# MainBoardR1.net
KiCad netlist of a schematic drawn in EAGLE
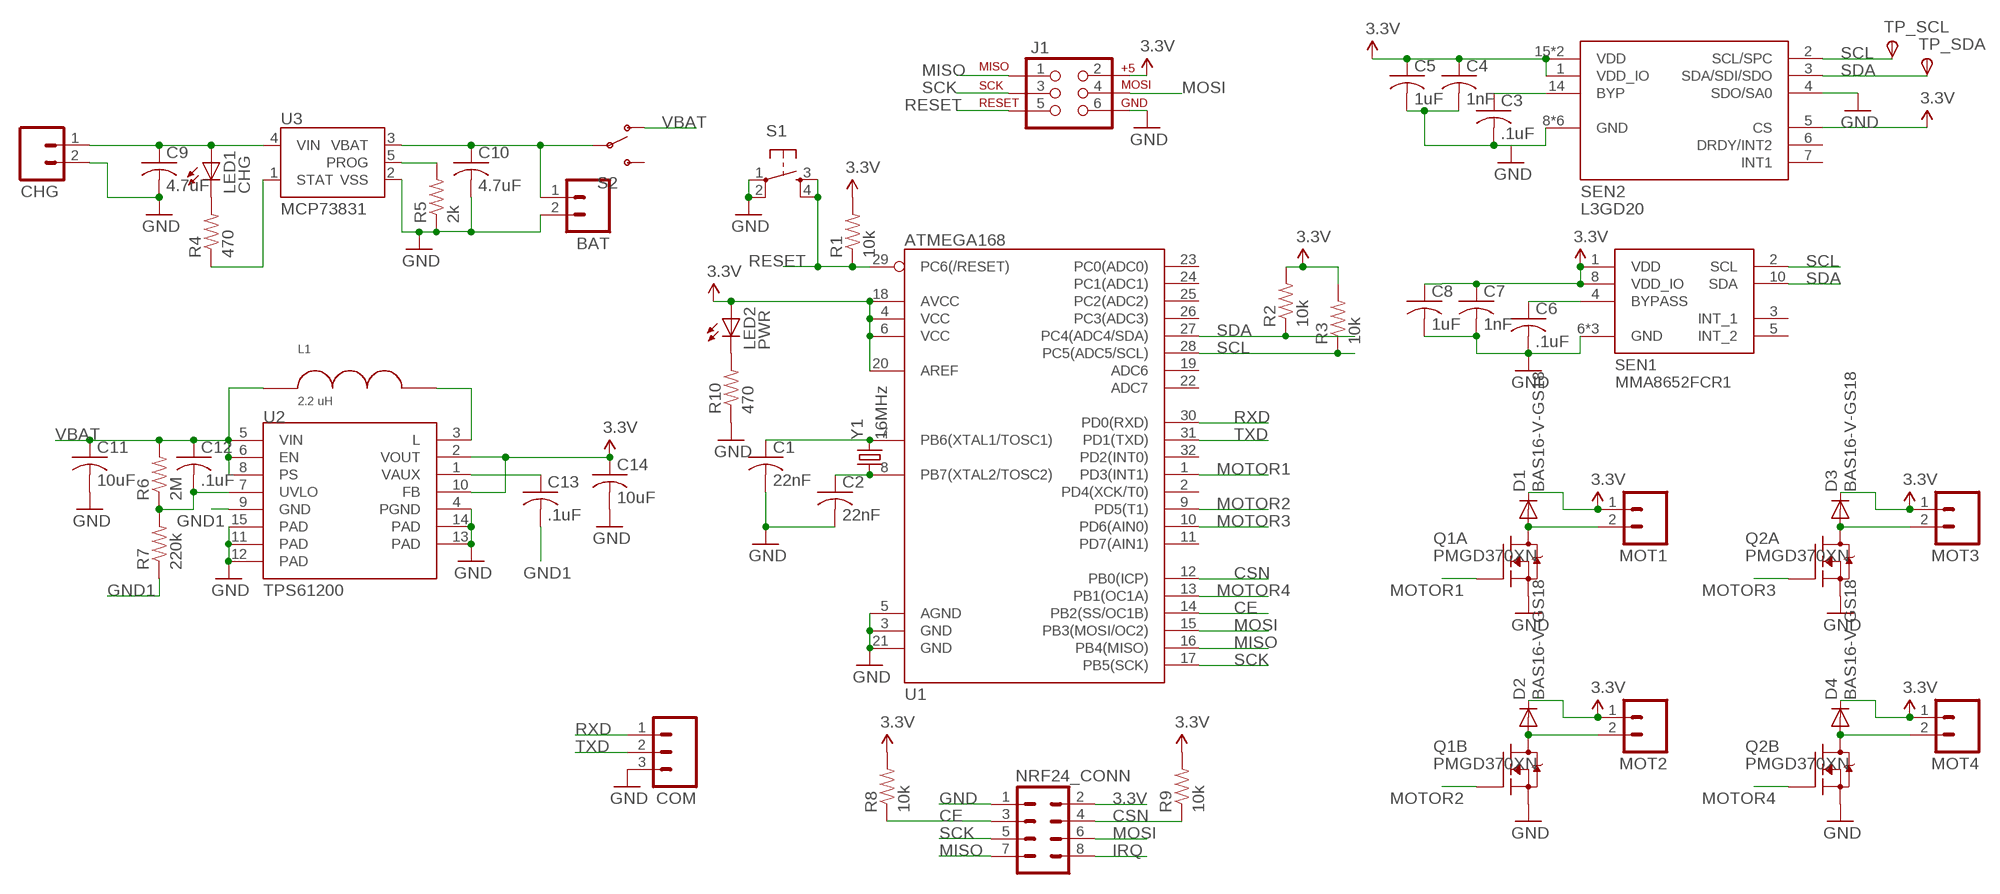
[diagram p0: schematic, sheet 1]

(export (version "E")
  (design (tool "Eeschema 10.0.6"))
  (components
    (comp (ref "BAT")
      (value "M02LOCK_LONGPADS")
      (footprint "eagle-import:1X02_LOCK_LONGPADS")
      (libsource (lib "eagle-import") (part "M02LOCK_LONGPADS"))
    )
    (comp (ref "C1")
      (value "22nF")
      (footprint "eagle-import:C0805")
      (libsource (lib "eagle-import") (part "C-USC0805"))
    )
    (comp (ref "C2")
      (value "22nF")
      (footprint "eagle-import:C0805")
      (libsource (lib "eagle-import") (part "C-USC0805"))
    )
    (comp (ref "C3")
      (value ".1uF")
      (footprint "eagle-import:C0805")
      (libsource (lib "eagle-import") (part "C-USC0805"))
    )
    (comp (ref "C4")
      (value "1nF")
      (footprint "eagle-import:C0805")
      (libsource (lib "eagle-import") (part "C-USC0805"))
    )
    (comp (ref "C5")
      (value "1uF")
      (footprint "eagle-import:C0805")
      (libsource (lib "eagle-import") (part "C-USC0805"))
    )
    (comp (ref "C6")
      (value ".1uF")
      (footprint "eagle-import:C0805")
      (libsource (lib "eagle-import") (part "C-USC0805"))
    )
    (comp (ref "C7")
      (value "1nF")
      (footprint "eagle-import:C0805")
      (libsource (lib "eagle-import") (part "C-USC0805"))
    )
    (comp (ref "C8")
      (value "1uF")
      (footprint "eagle-import:C0805")
      (libsource (lib "eagle-import") (part "C-USC0805"))
    )
    (comp (ref "C9")
      (value "4.7uF")
      (footprint "eagle-import:C0805")
      (libsource (lib "eagle-import") (part "C-USC0805"))
    )
    (comp (ref "C10")
      (value "4.7uF")
      (footprint "eagle-import:C0805")
      (libsource (lib "eagle-import") (part "C-USC0805"))
    )
    (comp (ref "C11")
      (value "10uF")
      (footprint "eagle-import:C0805")
      (libsource (lib "eagle-import") (part "C-USC0805"))
    )
    (comp (ref "C12")
      (value ".1uF")
      (footprint "eagle-import:C0805")
      (libsource (lib "eagle-import") (part "C-USC0805"))
    )
    (comp (ref "C13")
      (value ".1uF")
      (footprint "eagle-import:C0805")
      (libsource (lib "eagle-import") (part "C-USC0805"))
    )
    (comp (ref "C14")
      (value "10uF")
      (footprint "eagle-import:C0805")
      (libsource (lib "eagle-import") (part "C-USC0805"))
    )
    (comp (ref "CHG")
      (value "M02LOCK_LONGPADS")
      (footprint "eagle-import:1X02_LOCK_LONGPADS")
      (libsource (lib "eagle-import") (part "M02LOCK_LONGPADS"))
    )
    (comp (ref "COM")
      (value "M03LONGPADS")
      (footprint "eagle-import:1X03_LONGPADS")
      (libsource (lib "eagle-import") (part "M03LONGPADS"))
    )
    (comp (ref "D1")
      (value "BAS16-V-GS18")
      (footprint "eagle-import:SOT23")
      (libsource (lib "eagle-import") (part "BAS16-V-GS18"))
    )
    (comp (ref "D2")
      (value "BAS16-V-GS18")
      (footprint "eagle-import:SOT23")
      (libsource (lib "eagle-import") (part "BAS16-V-GS18"))
    )
    (comp (ref "D3")
      (value "BAS16-V-GS18")
      (footprint "eagle-import:SOT23")
      (libsource (lib "eagle-import") (part "BAS16-V-GS18"))
    )
    (comp (ref "D4")
      (value "BAS16-V-GS18")
      (footprint "eagle-import:SOT23")
      (libsource (lib "eagle-import") (part "BAS16-V-GS18"))
    )
    (comp (ref "J1")
      (value "AVR_SPI_PRG_62X3_LOCK")
      (footprint "eagle-import:2X3_LOCK")
      (libsource (lib "eagle-import") (part "AVR_SPI_PRG_62X3_LOCK"))
    )
    (comp (ref "L1")
      (value "2.2 uH")
      (footprint "eagle-import:2518")
      (libsource (lib "eagle-import") (part "BRHL2518T2R2M"))
    )
    (comp (ref "LED1")
      (value "CHG")
      (footprint "eagle-import:LED-1206")
      (libsource (lib "eagle-import") (part "LED1206"))
    )
    (comp (ref "LED2")
      (value "PWR")
      (footprint "eagle-import:LED-1206")
      (libsource (lib "eagle-import") (part "LED1206"))
    )
    (comp (ref "MOT1")
      (value "M02LOCK_LONGPADS")
      (footprint "eagle-import:1X02_LOCK_LONGPADS")
      (libsource (lib "eagle-import") (part "M02LOCK_LONGPADS"))
    )
    (comp (ref "MOT2")
      (value "M02LOCK_LONGPADS")
      (footprint "eagle-import:1X02_LOCK_LONGPADS")
      (libsource (lib "eagle-import") (part "M02LOCK_LONGPADS"))
    )
    (comp (ref "MOT3")
      (value "M02LOCK_LONGPADS")
      (footprint "eagle-import:1X02_LOCK_LONGPADS")
      (libsource (lib "eagle-import") (part "M02LOCK_LONGPADS"))
    )
    (comp (ref "MOT4")
      (value "M02LOCK_LONGPADS")
      (footprint "eagle-import:1X02_LOCK_LONGPADS")
      (libsource (lib "eagle-import") (part "M02LOCK_LONGPADS"))
    )
    (comp (ref "NRF24_CONN")
      (value "M04X2")
      (footprint "eagle-import:2X4")
      (libsource (lib "eagle-import") (part "M04X2"))
    )
    (comp (ref "Q1")
      (value "PMGD370XN")
      (footprint "eagle-import:SOT363_INFINEON")
      (libsource (lib "eagle-import") (part "PMGD370XN"))
    )
    (comp (ref "Q2")
      (value "PMGD370XN")
      (footprint "eagle-import:SOT363_INFINEON")
      (libsource (lib "eagle-import") (part "PMGD370XN"))
    )
    (comp (ref "R1")
      (value "10k")
      (footprint "eagle-import:0805")
      (libsource (lib "eagle-import") (part "RESISTOR0805-RES"))
    )
    (comp (ref "R2")
      (value "10k")
      (footprint "eagle-import:0805")
      (libsource (lib "eagle-import") (part "RESISTOR0805-RES"))
    )
    (comp (ref "R3")
      (value "10k")
      (footprint "eagle-import:0805")
      (libsource (lib "eagle-import") (part "RESISTOR0805-RES"))
    )
    (comp (ref "R4")
      (value "470")
      (footprint "eagle-import:0805")
      (libsource (lib "eagle-import") (part "RESISTOR0805-RES"))
    )
    (comp (ref "R5")
      (value "2k")
      (footprint "eagle-import:0805")
      (libsource (lib "eagle-import") (part "RESISTOR0805-RES"))
    )
    (comp (ref "R6")
      (value "2M")
      (footprint "eagle-import:0805")
      (libsource (lib "eagle-import") (part "RESISTOR0805-RES"))
    )
    (comp (ref "R7")
      (value "220k")
      (footprint "eagle-import:0805")
      (libsource (lib "eagle-import") (part "RESISTOR0805-RES"))
    )
    (comp (ref "R8")
      (value "10k")
      (footprint "eagle-import:0805")
      (libsource (lib "eagle-import") (part "RESISTOR0805-RES"))
    )
    (comp (ref "R9")
      (value "10k")
      (footprint "eagle-import:0805")
      (libsource (lib "eagle-import") (part "RESISTOR0805-RES"))
    )
    (comp (ref "R10")
      (value "470")
      (footprint "eagle-import:0805")
      (libsource (lib "eagle-import") (part "RESISTOR0805-RES"))
    )
    (comp (ref "S1")
      (value "TAC_SWITCHSMD")
      (footprint "eagle-import:TACTILE_SWITCH_SMD")
      (libsource (lib "eagle-import") (part "TAC_SWITCHSMD"))
    )
    (comp (ref "S2")
      (value "SWITCH-SPST-SMD-A")
      (footprint "eagle-import:SWITCH-SPST-SMD-A")
      (libsource (lib "eagle-import") (part "SWITCH-SPST-SMD-A"))
    )
    (comp (ref "SEN1")
      (value "MMA8652FCR1")
      (footprint "eagle-import:10_PIN_DFN")
      (libsource (lib "eagle-import") (part "MMA8652FCR1"))
    )
    (comp (ref "SEN2")
      (value "L3GD20")
      (footprint "eagle-import:LGA-16")
      (libsource (lib "eagle-import") (part "L3GD20"))
    )
    (comp (ref "TP_SCL")
      (value "TPSTP14SQ")
      (footprint "eagle-import:TP14SQ")
      (libsource (lib "eagle-import") (part "TPSTP14SQ"))
    )
    (comp (ref "TP_SDA")
      (value "TPSTP14SQ")
      (footprint "eagle-import:TP14SQ")
      (libsource (lib "eagle-import") (part "TPSTP14SQ"))
    )
    (comp (ref "U1")
      (value "ATMEGA168")
      (footprint "eagle-import:TQFP32-08")
      (libsource (lib "eagle-import") (part "ATMEGA168"))
    )
    (comp (ref "U2")
      (value "TPS61200")
      (footprint "eagle-import:QFN-10_PAD")
      (libsource (lib "eagle-import") (part "TPS61200"))
    )
    (comp (ref "U3")
      (value "MCP73831")
      (footprint "eagle-import:SOT23-5")
      (libsource (lib "eagle-import") (part "MCP73831"))
    )
    (comp (ref "Y1")
      (value "16MHz")
      (footprint "eagle-import:CRYSTAL-SMD-5X3")
      (libsource (lib "eagle-import") (part "CRYSTAL5X3"))
    )
  )
  (nets
    (net (code "1") (name "/CE") (class "Default")
      (node (ref "NRF24_CONN") (pin "3") (pinfunction "3_3") (pintype "passive"))
      (node (ref "R8") (pin "1") (pinfunction "1_1") (pintype "passive"))
      (node (ref "U1") (pin "14") (pinfunction "PB2(SS/OC1B)_14") (pintype "bidirectional"))
    )
    (net (code "2") (name "/CSN") (class "Default")
      (node (ref "NRF24_CONN") (pin "4") (pinfunction "4_4") (pintype "passive"))
      (node (ref "R9") (pin "1") (pinfunction "1_1") (pintype "passive"))
      (node (ref "U1") (pin "12") (pinfunction "PB0(ICP)_12") (pintype "bidirectional"))
    )
    (net (code "3") (name "/GND1") (class "Default")
      (node (ref "C13") (pin "2") (pinfunction "2_2") (pintype "passive"))
      (node (ref "R7") (pin "1") (pinfunction "1_1") (pintype "passive"))
      (node (ref "U2") (pin "9") (pinfunction "GND_9") (pintype "power_in"))
    )
    (net (code "4") (name "/IRQ") (class "Default")
      (node (ref "NRF24_CONN") (pin "8") (pinfunction "8_8") (pintype "passive"))
    )
    (net (code "5") (name "/MISO") (class "Default")
      (node (ref "J1") (pin "1") (pinfunction "1_1") (pintype "passive"))
      (node (ref "NRF24_CONN") (pin "7") (pinfunction "7_7") (pintype "passive"))
      (node (ref "U1") (pin "16") (pinfunction "PB4(MISO)_16") (pintype "bidirectional"))
    )
    (net (code "6") (name "/MOSI") (class "Default")
      (node (ref "J1") (pin "4") (pinfunction "4_4") (pintype "passive"))
      (node (ref "NRF24_CONN") (pin "6") (pinfunction "6_6") (pintype "passive"))
      (node (ref "U1") (pin "15") (pinfunction "PB3(MOSI/OC2)_15") (pintype "bidirectional"))
    )
    (net (code "7") (name "/MOTOR1") (class "Default")
      (node (ref "Q1") (pin "2") (pinfunction "G_2") (pintype "passive"))
      (node (ref "U1") (pin "1") (pinfunction "PD3(INT1)_1") (pintype "bidirectional"))
    )
    (net (code "8") (name "/MOTOR2") (class "Default")
      (node (ref "Q1") (pin "5") (pinfunction "G_5") (pintype "passive"))
      (node (ref "U1") (pin "9") (pinfunction "PD5(T1)_9") (pintype "bidirectional"))
    )
    (net (code "9") (name "/MOTOR3") (class "Default")
      (node (ref "Q2") (pin "2") (pinfunction "G_2") (pintype "passive"))
      (node (ref "U1") (pin "10") (pinfunction "PD6(AIN0)_10") (pintype "bidirectional"))
    )
    (net (code "10") (name "/MOTOR4") (class "Default")
      (node (ref "Q2") (pin "5") (pinfunction "G_5") (pintype "passive"))
      (node (ref "U1") (pin "13") (pinfunction "PB1(OC1A)_13") (pintype "bidirectional"))
    )
    (net (code "11") (name "/RESET") (class "Default")
      (node (ref "J1") (pin "5") (pinfunction "5_5") (pintype "passive"))
      (node (ref "R1") (pin "1") (pinfunction "1_1") (pintype "passive"))
      (node (ref "S1") (pin "3") (pinfunction "3_3") (pintype "passive"))
      (node (ref "S1") (pin "4") (pinfunction "4_4") (pintype "passive"))
      (node (ref "U1") (pin "29") (pinfunction "PC6(/RESET)_29") (pintype "bidirectional"))
    )
    (net (code "12") (name "/RXD") (class "Default")
      (node (ref "COM") (pin "1") (pinfunction "1_1") (pintype "passive"))
      (node (ref "U1") (pin "30") (pinfunction "PD0(RXD)_30") (pintype "bidirectional"))
    )
    (net (code "13") (name "/SCK") (class "Default")
      (node (ref "J1") (pin "3") (pinfunction "3_3") (pintype "passive"))
      (node (ref "NRF24_CONN") (pin "5") (pinfunction "5_5") (pintype "passive"))
      (node (ref "U1") (pin "17") (pinfunction "PB5(SCK)_17") (pintype "bidirectional"))
    )
    (net (code "14") (name "/SCL") (class "Default")
      (node (ref "R3") (pin "1") (pinfunction "1_1") (pintype "passive"))
      (node (ref "SEN1") (pin "2") (pinfunction "SCL_2") (pintype "bidirectional"))
      (node (ref "SEN2") (pin "2") (pinfunction "SCL/SPC_2") (pintype "bidirectional"))
      (node (ref "TP_SCL") (pin "TP") (pinfunction "PP_TP") (pintype "input"))
      (node (ref "U1") (pin "28") (pinfunction "PC5(ADC5/SCL)_28") (pintype "bidirectional"))
    )
    (net (code "15") (name "/SDA") (class "Default")
      (node (ref "R2") (pin "1") (pinfunction "1_1") (pintype "passive"))
      (node (ref "SEN1") (pin "10") (pinfunction "SDA_10") (pintype "bidirectional"))
      (node (ref "SEN2") (pin "3") (pinfunction "SDA/SDI/SDO_3") (pintype "bidirectional"))
      (node (ref "TP_SDA") (pin "TP") (pinfunction "PP_TP") (pintype "input"))
      (node (ref "U1") (pin "27") (pinfunction "PC4(ADC4/SDA)_27") (pintype "bidirectional"))
    )
    (net (code "16") (name "/TXD") (class "Default")
      (node (ref "COM") (pin "2") (pinfunction "2_2") (pintype "passive"))
      (node (ref "U1") (pin "31") (pinfunction "PD1(TXD)_31") (pintype "bidirectional"))
    )
    (net (code "17") (name "/VBAT") (class "Default")
      (node (ref "C11") (pin "1") (pinfunction "1_1") (pintype "passive"))
      (node (ref "C12") (pin "1") (pinfunction "1_1") (pintype "passive"))
      (node (ref "L1") (pin "P$1") (pinfunction "1_P$1") (pintype "bidirectional"))
      (node (ref "R6") (pin "2") (pinfunction "2_2") (pintype "passive"))
      (node (ref "S2") (pin "1") (pinfunction "O_1") (pintype "passive"))
      (node (ref "U2") (pin "5") (pinfunction "VIN_5") (pintype "power_in"))
      (node (ref "U2") (pin "6") (pinfunction "EN_6") (pintype "input"))
      (node (ref "U2") (pin "8") (pinfunction "PS_8") (pintype "input"))
    )
    (net (code "18") (name "3.3V") (class "Default")
      (node (ref "C14") (pin "1") (pinfunction "1_1") (pintype "passive"))
      (node (ref "C4") (pin "1") (pinfunction "1_1") (pintype "passive"))
      (node (ref "C5") (pin "1") (pinfunction "1_1") (pintype "passive"))
      (node (ref "C7") (pin "1") (pinfunction "1_1") (pintype "passive"))
      (node (ref "C8") (pin "1") (pinfunction "1_1") (pintype "passive"))
      (node (ref "D1") (pin "3") (pinfunction "C_3") (pintype "passive"))
      (node (ref "D2") (pin "3") (pinfunction "C_3") (pintype "passive"))
      (node (ref "D3") (pin "3") (pinfunction "C_3") (pintype "passive"))
      (node (ref "D4") (pin "3") (pinfunction "C_3") (pintype "passive"))
      (node (ref "J1") (pin "2") (pinfunction "2_2") (pintype "passive"))
      (node (ref "LED2") (pin "A") (pinfunction "A_A") (pintype "passive"))
      (node (ref "MOT1") (pin "1") (pinfunction "1_1") (pintype "passive"))
      (node (ref "MOT2") (pin "1") (pinfunction "1_1") (pintype "passive"))
      (node (ref "MOT3") (pin "1") (pinfunction "1_1") (pintype "passive"))
      (node (ref "MOT4") (pin "1") (pinfunction "1_1") (pintype "passive"))
      (node (ref "NRF24_CONN") (pin "2") (pinfunction "2_2") (pintype "passive"))
      (node (ref "R1") (pin "2") (pinfunction "2_2") (pintype "passive"))
      (node (ref "R2") (pin "2") (pinfunction "2_2") (pintype "passive"))
      (node (ref "R3") (pin "2") (pinfunction "2_2") (pintype "passive"))
      (node (ref "R8") (pin "2") (pinfunction "2_2") (pintype "passive"))
      (node (ref "R9") (pin "2") (pinfunction "2_2") (pintype "passive"))
      (node (ref "SEN1") (pin "1") (pinfunction "VDD_1") (pintype "bidirectional"))
      (node (ref "SEN1") (pin "8") (pinfunction "VDD_IO_8") (pintype "bidirectional"))
      (node (ref "SEN2") (pin "1") (pinfunction "VDD_IO_1") (pintype "bidirectional"))
      (node (ref "SEN2") (pin "15") (pinfunction "VDD_15") (pintype "bidirectional"))
      (node (ref "SEN2") (pin "16") (pinfunction "VDD_16") (pintype "bidirectional"))
      (node (ref "SEN2") (pin "5") (pinfunction "CS_5") (pintype "bidirectional"))
      (node (ref "U1") (pin "18") (pinfunction "AVCC_18") (pintype "bidirectional"))
      (node (ref "U1") (pin "20") (pinfunction "AREF_20") (pintype "bidirectional"))
      (node (ref "U1") (pin "4") (pinfunction "VCC_4") (pintype "bidirectional"))
      (node (ref "U1") (pin "6") (pinfunction "VCC_6") (pintype "bidirectional"))
      (node (ref "U2") (pin "10") (pinfunction "FB_10") (pintype "passive"))
      (node (ref "U2") (pin "2") (pinfunction "VOUT_2") (pintype "passive"))
    )
    (net (code "19") (name "GND") (class "Default")
      (node (ref "BAT") (pin "2") (pinfunction "2_2") (pintype "passive"))
      (node (ref "C1") (pin "2") (pinfunction "2_2") (pintype "passive"))
      (node (ref "C10") (pin "2") (pinfunction "2_2") (pintype "passive"))
      (node (ref "C11") (pin "2") (pinfunction "2_2") (pintype "passive"))
      (node (ref "C14") (pin "2") (pinfunction "2_2") (pintype "passive"))
      (node (ref "C2") (pin "2") (pinfunction "2_2") (pintype "passive"))
      (node (ref "C3") (pin "2") (pinfunction "2_2") (pintype "passive"))
      (node (ref "C4") (pin "2") (pinfunction "2_2") (pintype "passive"))
      (node (ref "C5") (pin "2") (pinfunction "2_2") (pintype "passive"))
      (node (ref "C6") (pin "2") (pinfunction "2_2") (pintype "passive"))
      (node (ref "C7") (pin "2") (pinfunction "2_2") (pintype "passive"))
      (node (ref "C8") (pin "2") (pinfunction "2_2") (pintype "passive"))
      (node (ref "C9") (pin "2") (pinfunction "2_2") (pintype "passive"))
      (node (ref "CHG") (pin "2") (pinfunction "2_2") (pintype "passive"))
      (node (ref "COM") (pin "3") (pinfunction "3_3") (pintype "passive"))
      (node (ref "J1") (pin "6") (pinfunction "6_6") (pintype "passive"))
      (node (ref "NRF24_CONN") (pin "1") (pinfunction "1_1") (pintype "passive"))
      (node (ref "Q1") (pin "1") (pinfunction "S_1") (pintype "passive"))
      (node (ref "Q1") (pin "4") (pinfunction "S_4") (pintype "passive"))
      (node (ref "Q2") (pin "1") (pinfunction "S_1") (pintype "passive"))
      (node (ref "Q2") (pin "4") (pinfunction "S_4") (pintype "passive"))
      (node (ref "R10") (pin "1") (pinfunction "1_1") (pintype "passive"))
      (node (ref "R5") (pin "1") (pinfunction "1_1") (pintype "passive"))
      (node (ref "S1") (pin "1") (pinfunction "1_1") (pintype "passive"))
      (node (ref "S1") (pin "2") (pinfunction "2_2") (pintype "passive"))
      (node (ref "SEN1") (pin "6") (pinfunction "GND_6") (pintype "bidirectional"))
      (node (ref "SEN1") (pin "7") (pinfunction "GND_7") (pintype "bidirectional"))
      (node (ref "SEN1") (pin "9") (pinfunction "GND_9") (pintype "bidirectional"))
      (node (ref "SEN2") (pin "10") (pinfunction "GND_10") (pintype "bidirectional"))
      (node (ref "SEN2") (pin "11") (pinfunction "GND_11") (pintype "bidirectional"))
      (node (ref "SEN2") (pin "12") (pinfunction "GND_12") (pintype "bidirectional"))
      (node (ref "SEN2") (pin "13") (pinfunction "GND_13") (pintype "bidirectional"))
      (node (ref "SEN2") (pin "4") (pinfunction "SDO/SA0_4") (pintype "bidirectional"))
      (node (ref "SEN2") (pin "8") (pinfunction "GND_8") (pintype "bidirectional"))
      (node (ref "SEN2") (pin "9") (pinfunction "GND_9") (pintype "bidirectional"))
      (node (ref "U1") (pin "21") (pinfunction "GND_21") (pintype "bidirectional"))
      (node (ref "U1") (pin "3") (pinfunction "GND_3") (pintype "bidirectional"))
      (node (ref "U1") (pin "5") (pinfunction "AGND_5") (pintype "bidirectional"))
      (node (ref "U2") (pin "11") (pinfunction "PAD_11") (pintype "power_in"))
      (node (ref "U2") (pin "12") (pinfunction "PAD_12") (pintype "power_in"))
      (node (ref "U2") (pin "13") (pinfunction "PAD_13") (pintype "power_in"))
      (node (ref "U2") (pin "14") (pinfunction "PAD_14") (pintype "power_in"))
      (node (ref "U2") (pin "15") (pinfunction "PAD_15") (pintype "power_in"))
      (node (ref "U2") (pin "4") (pinfunction "PGND_4") (pintype "power_in"))
      (node (ref "U3") (pin "2") (pinfunction "VSS_2") (pintype "power_in"))
    )
    (net (code "20") (name "Net-(D1-A)") (class "Default")
      (node (ref "D1") (pin "1") (pinfunction "A_1") (pintype "passive"))
      (node (ref "MOT1") (pin "2") (pinfunction "2_2") (pintype "passive"))
      (node (ref "Q1") (pin "6") (pinfunction "D_6") (pintype "passive"))
    )
    (net (code "21") (name "Net-(D2-A)") (class "Default")
      (node (ref "D2") (pin "1") (pinfunction "A_1") (pintype "passive"))
      (node (ref "MOT2") (pin "2") (pinfunction "2_2") (pintype "passive"))
      (node (ref "Q1") (pin "3") (pinfunction "D_3") (pintype "passive"))
    )
    (net (code "22") (name "Net-(D3-A)") (class "Default")
      (node (ref "D3") (pin "1") (pinfunction "A_1") (pintype "passive"))
      (node (ref "MOT3") (pin "2") (pinfunction "2_2") (pintype "passive"))
      (node (ref "Q2") (pin "6") (pinfunction "D_6") (pintype "passive"))
    )
    (net (code "23") (name "Net-(D4-A)") (class "Default")
      (node (ref "D4") (pin "1") (pinfunction "A_1") (pintype "passive"))
      (node (ref "MOT4") (pin "2") (pinfunction "2_2") (pintype "passive"))
      (node (ref "Q2") (pin "3") (pinfunction "D_3") (pintype "passive"))
    )
    (net (code "24") (name "Net-(L1-2)") (class "Default")
      (node (ref "L1") (pin "P$2") (pinfunction "2_P$2") (pintype "bidirectional"))
      (node (ref "U2") (pin "3") (pinfunction "L_3") (pintype "passive"))
    )
    (net (code "25") (name "Net-(LED1-PadC)") (class "Default")
      (node (ref "LED1") (pin "C") (pinfunction "C_C") (pintype "passive"))
      (node (ref "R4") (pin "2") (pinfunction "2_2") (pintype "passive"))
    )
    (net (code "26") (name "Net-(LED2-PadC)") (class "Default")
      (node (ref "LED2") (pin "C") (pinfunction "C_C") (pintype "passive"))
      (node (ref "R10") (pin "2") (pinfunction "2_2") (pintype "passive"))
    )
    (net (code "27") (name "Net-(S2-P)") (class "Default")
      (node (ref "BAT") (pin "1") (pinfunction "1_1") (pintype "passive"))
      (node (ref "C10") (pin "1") (pinfunction "1_1") (pintype "passive"))
      (node (ref "S2") (pin "2") (pinfunction "P_2") (pintype "passive"))
      (node (ref "U3") (pin "3") (pinfunction "VBAT_3") (pintype "power_in"))
    )
    (net (code "28") (name "Net-(SEN1-BYPASS)") (class "Default")
      (node (ref "C6") (pin "1") (pinfunction "1_1") (pintype "passive"))
      (node (ref "SEN1") (pin "4") (pinfunction "BYPASS_4") (pintype "bidirectional"))
    )
    (net (code "29") (name "Net-(SEN2-BYP)") (class "Default")
      (node (ref "C3") (pin "1") (pinfunction "1_1") (pintype "passive"))
      (node (ref "SEN2") (pin "14") (pinfunction "BYP_14") (pintype "bidirectional"))
    )
    (net (code "30") (name "Net-(U1-PB6(XTAL1{slash}TOSC1))") (class "Default")
      (node (ref "C1") (pin "1") (pinfunction "1_1") (pintype "passive"))
      (node (ref "U1") (pin "7") (pinfunction "PB6(XTAL1/TOSC1)_7") (pintype "bidirectional"))
      (node (ref "Y1") (pin "3") (pinfunction "2_3") (pintype "passive"))
    )
    (net (code "31") (name "Net-(U1-PB7(XTAL2{slash}TOSC2))") (class "Default")
      (node (ref "C2") (pin "1") (pinfunction "1_1") (pintype "passive"))
      (node (ref "U1") (pin "8") (pinfunction "PB7(XTAL2/TOSC2)_8") (pintype "bidirectional"))
      (node (ref "Y1") (pin "1") (pinfunction "1_1") (pintype "passive"))
    )
    (net (code "32") (name "Net-(U2-UVLO)") (class "Default")
      (node (ref "C12") (pin "2") (pinfunction "2_2") (pintype "passive"))
      (node (ref "R6") (pin "1") (pinfunction "1_1") (pintype "passive"))
      (node (ref "R7") (pin "2") (pinfunction "2_2") (pintype "passive"))
      (node (ref "U2") (pin "7") (pinfunction "UVLO_7") (pintype "passive"))
    )
    (net (code "33") (name "Net-(U2-VAUX)") (class "Default")
      (node (ref "C13") (pin "1") (pinfunction "1_1") (pintype "passive"))
      (node (ref "U2") (pin "1") (pinfunction "VAUX_1") (pintype "passive"))
    )
    (net (code "34") (name "Net-(U3-PROG)") (class "Default")
      (node (ref "R5") (pin "2") (pinfunction "2_2") (pintype "passive"))
      (node (ref "U3") (pin "5") (pinfunction "PROG_5") (pintype "input"))
    )
    (net (code "35") (name "Net-(U3-STAT)") (class "Default")
      (node (ref "R4") (pin "1") (pinfunction "1_1") (pintype "passive"))
      (node (ref "U3") (pin "1") (pinfunction "STAT_1") (pintype "output"))
    )
    (net (code "36") (name "Net-(U3-VIN)") (class "Default")
      (node (ref "C9") (pin "1") (pinfunction "1_1") (pintype "passive"))
      (node (ref "CHG") (pin "1") (pinfunction "1_1") (pintype "passive"))
      (node (ref "LED1") (pin "A") (pinfunction "A_A") (pintype "passive"))
      (node (ref "U3") (pin "4") (pinfunction "VIN_4") (pintype "power_in"))
    )
    (net (code "37") (name "unconnected-(S2-S-Pad3)") (class "Default")
      (node (ref "S2") (pin "3") (pinfunction "S_3") (pintype "passive"))
    )
    (net (code "38") (name "unconnected-(SEN1-INT_1-Pad3)") (class "Default")
      (node (ref "SEN1") (pin "3") (pinfunction "INT_1_3") (pintype "bidirectional"))
    )
    (net (code "39") (name "unconnected-(SEN1-INT_2-Pad5)") (class "Default")
      (node (ref "SEN1") (pin "5") (pinfunction "INT_2_5") (pintype "bidirectional"))
    )
    (net (code "40") (name "unconnected-(SEN2-DRDY{slash}INT2-Pad6)") (class "Default")
      (node (ref "SEN2") (pin "6") (pinfunction "DRDY/INT2_6") (pintype "bidirectional"))
    )
    (net (code "41") (name "unconnected-(SEN2-INT1-Pad7)") (class "Default")
      (node (ref "SEN2") (pin "7") (pinfunction "INT1_7") (pintype "bidirectional"))
    )
    (net (code "42") (name "unconnected-(U1-ADC6-Pad19)") (class "Default")
      (node (ref "U1") (pin "19") (pinfunction "ADC6_19") (pintype "bidirectional"))
    )
    (net (code "43") (name "unconnected-(U1-ADC7-Pad22)") (class "Default")
      (node (ref "U1") (pin "22") (pinfunction "ADC7_22") (pintype "bidirectional"))
    )
    (net (code "44") (name "unconnected-(U1-PC0(ADC0)-Pad23)") (class "Default")
      (node (ref "U1") (pin "23") (pinfunction "PC0(ADC0)_23") (pintype "bidirectional"))
    )
    (net (code "45") (name "unconnected-(U1-PC1(ADC1)-Pad24)") (class "Default")
      (node (ref "U1") (pin "24") (pinfunction "PC1(ADC1)_24") (pintype "bidirectional"))
    )
    (net (code "46") (name "unconnected-(U1-PC2(ADC2)-Pad25)") (class "Default")
      (node (ref "U1") (pin "25") (pinfunction "PC2(ADC2)_25") (pintype "bidirectional"))
    )
    (net (code "47") (name "unconnected-(U1-PC3(ADC3)-Pad26)") (class "Default")
      (node (ref "U1") (pin "26") (pinfunction "PC3(ADC3)_26") (pintype "bidirectional"))
    )
    (net (code "48") (name "unconnected-(U1-PD2(INT0)-Pad32)") (class "Default")
      (node (ref "U1") (pin "32") (pinfunction "PD2(INT0)_32") (pintype "bidirectional"))
    )
    (net (code "49") (name "unconnected-(U1-PD4(XCK{slash}T0)-Pad2)") (class "Default")
      (node (ref "U1") (pin "2") (pinfunction "PD4(XCK/T0)_2") (pintype "bidirectional"))
    )
    (net (code "50") (name "unconnected-(U1-PD7(AIN1)-Pad11)") (class "Default")
      (node (ref "U1") (pin "11") (pinfunction "PD7(AIN1)_11") (pintype "bidirectional"))
    )
  )
)
